# pcbthing.net
KiCad netlist of a schematic drawn in Altium Designer
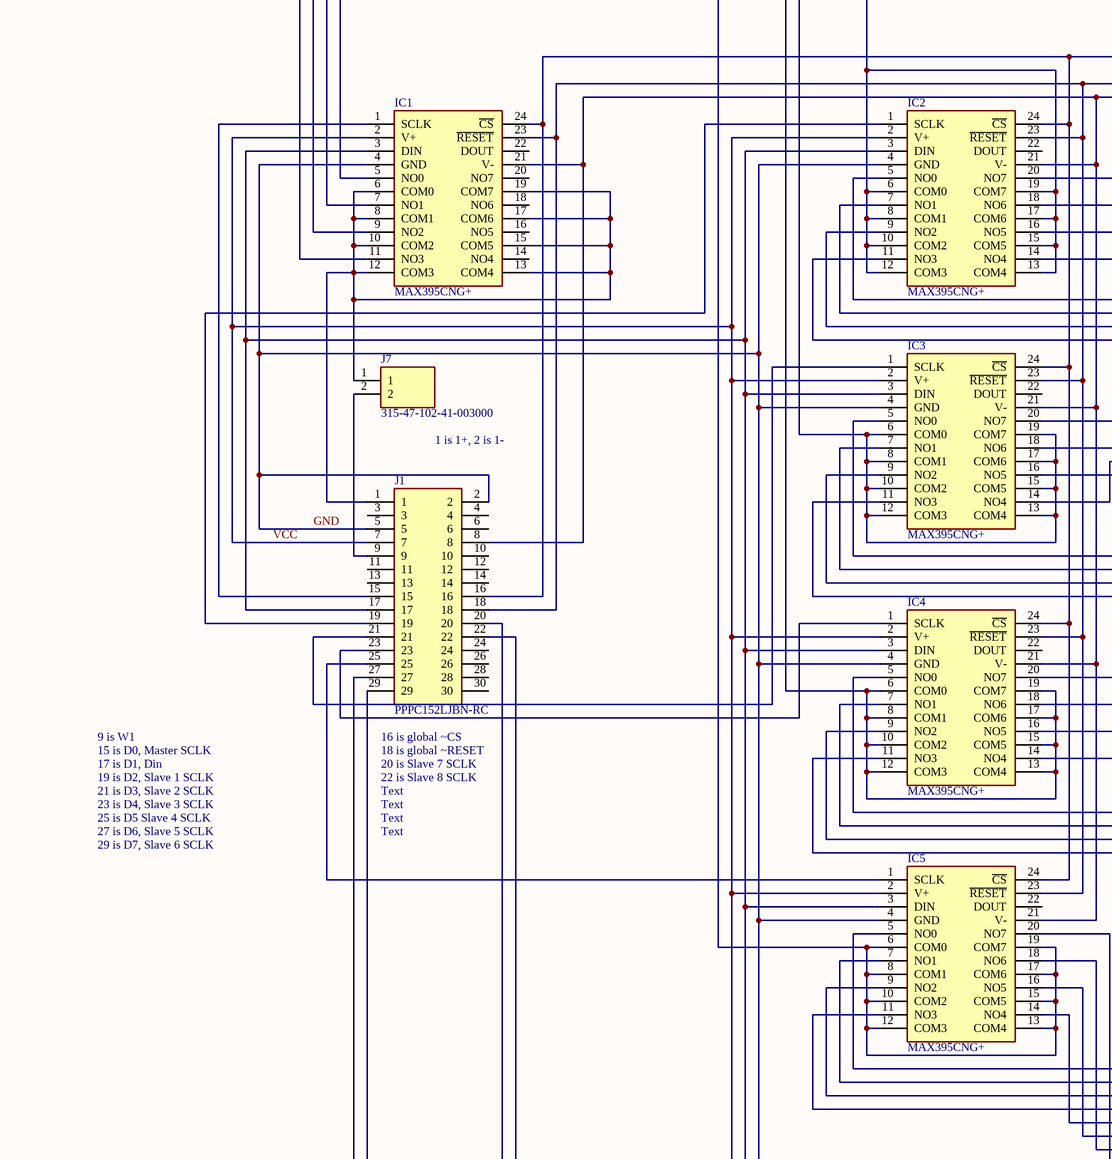
[diagram p0: pcbthing.SchDoc, left]
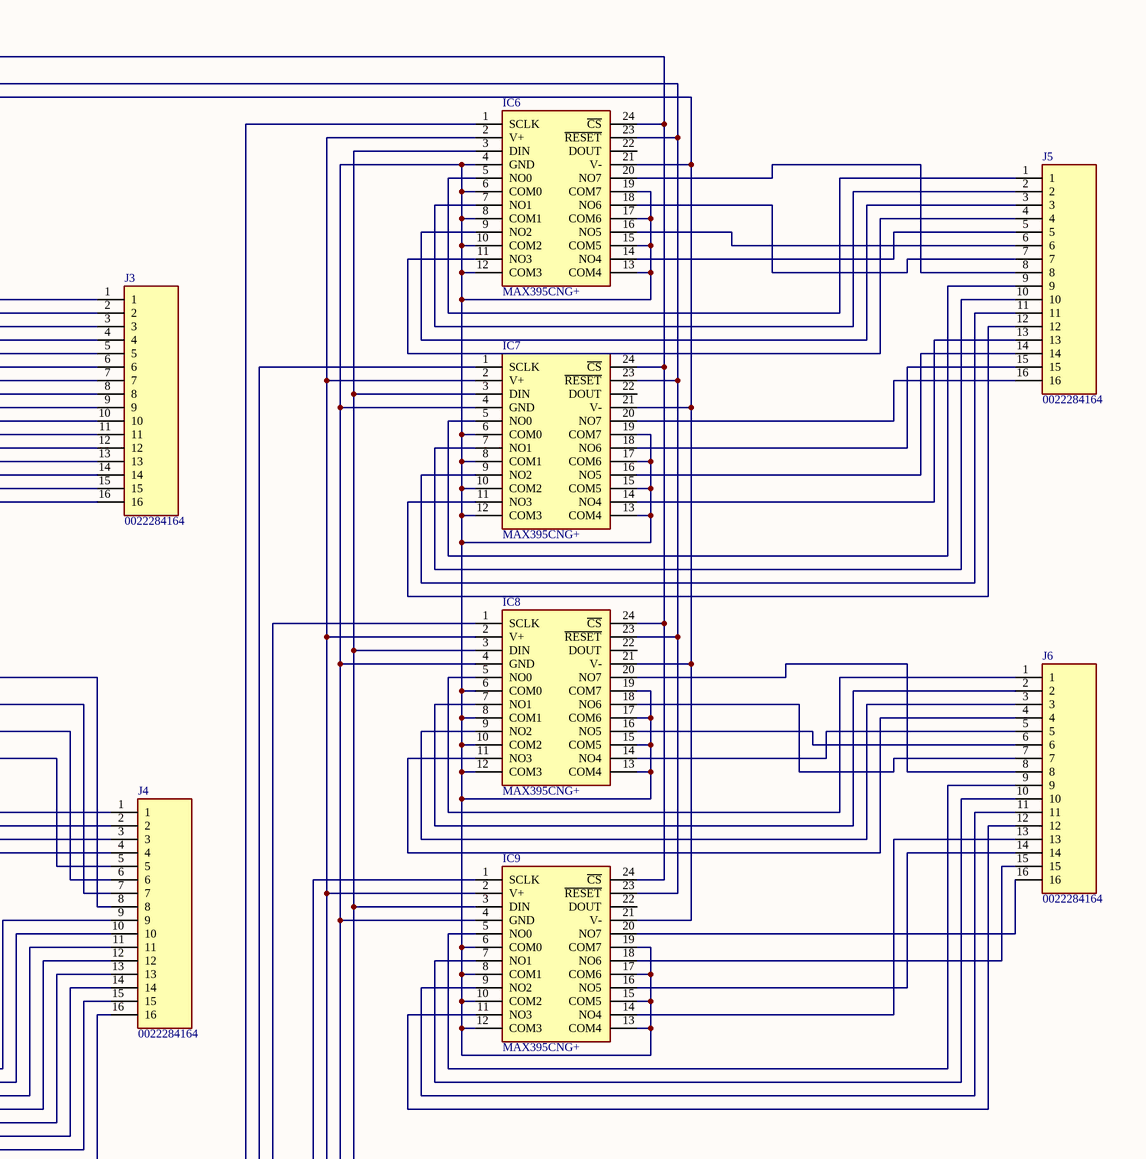
[diagram p1: pcbthing.SchDoc, right]

(export (version "E")
  (design (tool "Eeschema 10.0.6"))
  (components
    (comp (ref "IC1")
      (value "MAX395CNG+")
      (footprint "SamacSys:DIP794W56P254L3054H457Q24N")
      (description "Integrated Circuit")
      (fields (field (name "MOUSER PART NUMBER") "700-MAX395CNG"))
      (libsource (lib "*") (part "MAX395CNG+"))
    )
    (comp (ref "IC2")
      (value "MAX395CNG+")
      (footprint "SamacSys:DIP794W56P254L3054H457Q24N")
      (description "Integrated Circuit")
      (fields (field (name "MOUSER PART NUMBER") "700-MAX395CNG"))
      (libsource (lib "*") (part "MAX395CNG+"))
    )
    (comp (ref "IC3")
      (value "MAX395CNG+")
      (footprint "SamacSys:DIP794W56P254L3054H457Q24N")
      (description "Integrated Circuit")
      (fields (field (name "MOUSER PART NUMBER") "700-MAX395CNG"))
      (libsource (lib "*") (part "MAX395CNG+"))
    )
    (comp (ref "IC4")
      (value "MAX395CNG+")
      (footprint "SamacSys:DIP794W56P254L3054H457Q24N")
      (description "Integrated Circuit")
      (fields (field (name "MOUSER PART NUMBER") "700-MAX395CNG"))
      (libsource (lib "*") (part "MAX395CNG+"))
    )
    (comp (ref "IC5")
      (value "MAX395CNG+")
      (footprint "SamacSys:DIP794W56P254L3054H457Q24N")
      (description "Integrated Circuit")
      (fields (field (name "MOUSER PART NUMBER") "700-MAX395CNG"))
      (libsource (lib "*") (part "MAX395CNG+"))
    )
    (comp (ref "IC6")
      (value "MAX395CNG+")
      (footprint "SamacSys:DIP794W56P254L3054H457Q24N")
      (description "Integrated Circuit")
      (fields (field (name "MOUSER PART NUMBER") "700-MAX395CNG"))
      (libsource (lib "*") (part "MAX395CNG+"))
    )
    (comp (ref "IC7")
      (value "MAX395CNG+")
      (footprint "SamacSys:DIP794W56P254L3054H457Q24N")
      (description "Integrated Circuit")
      (fields (field (name "MOUSER PART NUMBER") "700-MAX395CNG"))
      (libsource (lib "*") (part "MAX395CNG+"))
    )
    (comp (ref "IC8")
      (value "MAX395CNG+")
      (footprint "SamacSys:DIP794W56P254L3054H457Q24N")
      (description "Integrated Circuit")
      (fields (field (name "MOUSER PART NUMBER") "700-MAX395CNG"))
      (libsource (lib "*") (part "MAX395CNG+"))
    )
    (comp (ref "IC9")
      (value "MAX395CNG+")
      (footprint "SamacSys:DIP794W56P254L3054H457Q24N")
      (description "Integrated Circuit")
      (fields (field (name "MOUSER PART NUMBER") "700-MAX395CNG"))
      (libsource (lib "*") (part "MAX395CNG+"))
    )
    (comp (ref "J1")
      (value "PPPC152LJBN-RC")
      (footprint "SamacSys:RHDRRA30W60P254X254_2X15_3860X850X528P")
      (description "Connector")
      (libsource (lib "*") (part "PPPC152LJBN-RC"))
    )
    (comp (ref "J3")
      (value "0022284164")
      (footprint "SamacSys:HDRV16W66P0X254_1X16_4064X249X1041P")
      (description "Connector")
      (libsource (lib "*") (part "0022284164"))
    )
    (comp (ref "J4")
      (value "0022284164")
      (footprint "SamacSys:HDRV16W66P0X254_1X16_4064X249X1041P")
      (description "Connector")
      (libsource (lib "*") (part "0022284164"))
    )
    (comp (ref "J5")
      (value "0022284164")
      (footprint "SamacSys:HDRV16W66P0X254_1X16_4064X249X1041P")
      (description "Connector")
      (libsource (lib "*") (part "0022284164"))
    )
    (comp (ref "J6")
      (value "0022284164")
      (footprint "SamacSys:HDRV16W66P0X254_1X16_4064X249X1041P")
      (description "Connector")
      (libsource (lib "*") (part "0022284164"))
    )
    (comp (ref "J7")
      (value "315-47-102-41-003000")
      (footprint "SamacSys:3154710241003000")
      (description "Connector")
      (fields (field (name "MOUSER PART NUMBER") "575-3154710241003000"))
      (libsource (lib "*") (part "315-47-102-41-003000"))
    )
  )
  (nets
    (net (code "1") (name "/GND") (class "Default")
      (node (ref "IC1") (pin "4") (pinfunction "GND_4") (pintype "passive"))
      (node (ref "IC2") (pin "4") (pinfunction "GND_4") (pintype "passive"))
      (node (ref "IC3") (pin "4") (pinfunction "GND_4") (pintype "passive"))
      (node (ref "IC4") (pin "4") (pinfunction "GND_4") (pintype "passive"))
      (node (ref "IC5") (pin "4") (pinfunction "GND_4") (pintype "passive"))
      (node (ref "IC6") (pin "10") (pinfunction "COM2_10") (pintype "passive"))
      (node (ref "IC6") (pin "12") (pinfunction "COM3_12") (pintype "passive"))
      (node (ref "IC6") (pin "13") (pinfunction "COM4_13") (pintype "passive"))
      (node (ref "IC6") (pin "15") (pinfunction "COM5_15") (pintype "passive"))
      (node (ref "IC6") (pin "17") (pinfunction "COM6_17") (pintype "passive"))
      (node (ref "IC6") (pin "19") (pinfunction "COM7_19") (pintype "passive"))
      (node (ref "IC6") (pin "4") (pinfunction "GND_4") (pintype "passive"))
      (node (ref "IC6") (pin "6") (pinfunction "COM0_6") (pintype "passive"))
      (node (ref "IC6") (pin "8") (pinfunction "COM1_8") (pintype "passive"))
      (node (ref "IC7") (pin "10") (pinfunction "COM2_10") (pintype "passive"))
      (node (ref "IC7") (pin "12") (pinfunction "COM3_12") (pintype "passive"))
      (node (ref "IC7") (pin "13") (pinfunction "COM4_13") (pintype "passive"))
      (node (ref "IC7") (pin "15") (pinfunction "COM5_15") (pintype "passive"))
      (node (ref "IC7") (pin "17") (pinfunction "COM6_17") (pintype "passive"))
      (node (ref "IC7") (pin "19") (pinfunction "COM7_19") (pintype "passive"))
      (node (ref "IC7") (pin "4") (pinfunction "GND_4") (pintype "passive"))
      (node (ref "IC7") (pin "6") (pinfunction "COM0_6") (pintype "passive"))
      (node (ref "IC7") (pin "8") (pinfunction "COM1_8") (pintype "passive"))
      (node (ref "IC8") (pin "10") (pinfunction "COM2_10") (pintype "passive"))
      (node (ref "IC8") (pin "12") (pinfunction "COM3_12") (pintype "passive"))
      (node (ref "IC8") (pin "13") (pinfunction "COM4_13") (pintype "passive"))
      (node (ref "IC8") (pin "15") (pinfunction "COM5_15") (pintype "passive"))
      (node (ref "IC8") (pin "17") (pinfunction "COM6_17") (pintype "passive"))
      (node (ref "IC8") (pin "19") (pinfunction "COM7_19") (pintype "passive"))
      (node (ref "IC8") (pin "4") (pinfunction "GND_4") (pintype "passive"))
      (node (ref "IC8") (pin "6") (pinfunction "COM0_6") (pintype "passive"))
      (node (ref "IC8") (pin "8") (pinfunction "COM1_8") (pintype "passive"))
      (node (ref "IC9") (pin "10") (pinfunction "COM2_10") (pintype "passive"))
      (node (ref "IC9") (pin "12") (pinfunction "COM3_12") (pintype "passive"))
      (node (ref "IC9") (pin "13") (pinfunction "COM4_13") (pintype "passive"))
      (node (ref "IC9") (pin "15") (pinfunction "COM5_15") (pintype "passive"))
      (node (ref "IC9") (pin "17") (pinfunction "COM6_17") (pintype "passive"))
      (node (ref "IC9") (pin "19") (pinfunction "COM7_19") (pintype "passive"))
      (node (ref "IC9") (pin "4") (pinfunction "GND_4") (pintype "passive"))
      (node (ref "IC9") (pin "6") (pinfunction "COM0_6") (pintype "passive"))
      (node (ref "IC9") (pin "8") (pinfunction "COM1_8") (pintype "passive"))
      (node (ref "J1") (pin "2") (pinfunction "2_2") (pintype "passive"))
      (node (ref "J1") (pin "5") (pinfunction "5_5") (pintype "passive"))
    )
    (net (code "2") (name "/VCC") (class "Default")
      (node (ref "IC1") (pin "2") (pinfunction "V+_2") (pintype "passive"))
      (node (ref "IC2") (pin "2") (pinfunction "V+_2") (pintype "passive"))
      (node (ref "IC3") (pin "2") (pinfunction "V+_2") (pintype "passive"))
      (node (ref "IC4") (pin "2") (pinfunction "V+_2") (pintype "passive"))
      (node (ref "IC5") (pin "2") (pinfunction "V+_2") (pintype "passive"))
      (node (ref "IC6") (pin "2") (pinfunction "V+_2") (pintype "passive"))
      (node (ref "IC7") (pin "2") (pinfunction "V+_2") (pintype "passive"))
      (node (ref "IC8") (pin "2") (pinfunction "V+_2") (pintype "passive"))
      (node (ref "IC9") (pin "2") (pinfunction "V+_2") (pintype "passive"))
      (node (ref "J1") (pin "7") (pinfunction "7_7") (pintype "passive"))
    )
    (net (code "3") (name "Net-(IC1-COM0)") (class "Default")
      (node (ref "IC1") (pin "10") (pinfunction "COM2_10") (pintype "passive"))
      (node (ref "IC1") (pin "12") (pinfunction "COM3_12") (pintype "passive"))
      (node (ref "IC1") (pin "13") (pinfunction "COM4_13") (pintype "passive"))
      (node (ref "IC1") (pin "15") (pinfunction "COM5_15") (pintype "passive"))
      (node (ref "IC1") (pin "17") (pinfunction "COM6_17") (pintype "passive"))
      (node (ref "IC1") (pin "19") (pinfunction "COM7_19") (pintype "passive"))
      (node (ref "IC1") (pin "6") (pinfunction "COM0_6") (pintype "passive"))
      (node (ref "IC1") (pin "8") (pinfunction "COM1_8") (pintype "passive"))
      (node (ref "J1") (pin "1") (pinfunction "1_1") (pintype "passive"))
      (node (ref "J7") (pin "1") (pinfunction "1_1") (pintype "passive"))
    )
    (net (code "4") (name "Net-(IC1-DIN)") (class "Default")
      (node (ref "IC1") (pin "3") (pinfunction "DIN_3") (pintype "passive"))
      (node (ref "IC2") (pin "3") (pinfunction "DIN_3") (pintype "passive"))
      (node (ref "IC3") (pin "3") (pinfunction "DIN_3") (pintype "passive"))
      (node (ref "IC4") (pin "3") (pinfunction "DIN_3") (pintype "passive"))
      (node (ref "IC5") (pin "3") (pinfunction "DIN_3") (pintype "passive"))
      (node (ref "IC6") (pin "3") (pinfunction "DIN_3") (pintype "passive"))
      (node (ref "IC7") (pin "3") (pinfunction "DIN_3") (pintype "passive"))
      (node (ref "IC8") (pin "3") (pinfunction "DIN_3") (pintype "passive"))
      (node (ref "IC9") (pin "3") (pinfunction "DIN_3") (pintype "passive"))
      (node (ref "J1") (pin "17") (pinfunction "17_17") (pintype "passive"))
    )
    (net (code "5") (name "Net-(IC1-NO0)") (class "Default")
      (node (ref "IC1") (pin "5") (pinfunction "NO0_5") (pintype "passive"))
      (node (ref "IC2") (pin "10") (pinfunction "COM2_10") (pintype "passive"))
      (node (ref "IC2") (pin "12") (pinfunction "COM3_12") (pintype "passive"))
      (node (ref "IC2") (pin "13") (pinfunction "COM4_13") (pintype "passive"))
      (node (ref "IC2") (pin "15") (pinfunction "COM5_15") (pintype "passive"))
      (node (ref "IC2") (pin "17") (pinfunction "COM6_17") (pintype "passive"))
      (node (ref "IC2") (pin "19") (pinfunction "COM7_19") (pintype "passive"))
      (node (ref "IC2") (pin "6") (pinfunction "COM0_6") (pintype "passive"))
      (node (ref "IC2") (pin "8") (pinfunction "COM1_8") (pintype "passive"))
    )
    (net (code "6") (name "Net-(IC1-NO1)") (class "Default")
      (node (ref "IC1") (pin "7") (pinfunction "NO1_7") (pintype "passive"))
      (node (ref "IC3") (pin "10") (pinfunction "COM2_10") (pintype "passive"))
      (node (ref "IC3") (pin "12") (pinfunction "COM3_12") (pintype "passive"))
      (node (ref "IC3") (pin "13") (pinfunction "COM4_13") (pintype "passive"))
      (node (ref "IC3") (pin "15") (pinfunction "COM5_15") (pintype "passive"))
      (node (ref "IC3") (pin "17") (pinfunction "COM6_17") (pintype "passive"))
      (node (ref "IC3") (pin "19") (pinfunction "COM7_19") (pintype "passive"))
      (node (ref "IC3") (pin "6") (pinfunction "COM0_6") (pintype "passive"))
      (node (ref "IC3") (pin "8") (pinfunction "COM1_8") (pintype "passive"))
    )
    (net (code "7") (name "Net-(IC1-NO2)") (class "Default")
      (node (ref "IC1") (pin "9") (pinfunction "NO2_9") (pintype "passive"))
      (node (ref "IC4") (pin "10") (pinfunction "COM2_10") (pintype "passive"))
      (node (ref "IC4") (pin "12") (pinfunction "COM3_12") (pintype "passive"))
      (node (ref "IC4") (pin "13") (pinfunction "COM4_13") (pintype "passive"))
      (node (ref "IC4") (pin "15") (pinfunction "COM5_15") (pintype "passive"))
      (node (ref "IC4") (pin "17") (pinfunction "COM6_17") (pintype "passive"))
      (node (ref "IC4") (pin "19") (pinfunction "COM7_19") (pintype "passive"))
      (node (ref "IC4") (pin "6") (pinfunction "COM0_6") (pintype "passive"))
      (node (ref "IC4") (pin "8") (pinfunction "COM1_8") (pintype "passive"))
    )
    (net (code "8") (name "Net-(IC1-NO3)") (class "Default")
      (node (ref "IC1") (pin "11") (pinfunction "NO3_11") (pintype "passive"))
      (node (ref "IC5") (pin "10") (pinfunction "COM2_10") (pintype "passive"))
      (node (ref "IC5") (pin "12") (pinfunction "COM3_12") (pintype "passive"))
      (node (ref "IC5") (pin "13") (pinfunction "COM4_13") (pintype "passive"))
      (node (ref "IC5") (pin "15") (pinfunction "COM5_15") (pintype "passive"))
      (node (ref "IC5") (pin "17") (pinfunction "COM6_17") (pintype "passive"))
      (node (ref "IC5") (pin "19") (pinfunction "COM7_19") (pintype "passive"))
      (node (ref "IC5") (pin "6") (pinfunction "COM0_6") (pintype "passive"))
      (node (ref "IC5") (pin "8") (pinfunction "COM1_8") (pintype "passive"))
    )
    (net (code "9") (name "Net-(IC1-SCLK)") (class "Default")
      (node (ref "IC1") (pin "1") (pinfunction "SCLK_1") (pintype "passive"))
      (node (ref "J1") (pin "15") (pinfunction "15_15") (pintype "passive"))
    )
    (net (code "10") (name "Net-(IC1-V-)") (class "Default")
      (node (ref "IC1") (pin "21") (pinfunction "V-_21") (pintype "passive"))
      (node (ref "IC2") (pin "21") (pinfunction "V-_21") (pintype "passive"))
      (node (ref "IC3") (pin "21") (pinfunction "V-_21") (pintype "passive"))
      (node (ref "IC4") (pin "21") (pinfunction "V-_21") (pintype "passive"))
      (node (ref "IC5") (pin "21") (pinfunction "V-_21") (pintype "passive"))
      (node (ref "IC6") (pin "21") (pinfunction "V-_21") (pintype "passive"))
      (node (ref "IC7") (pin "21") (pinfunction "V-_21") (pintype "passive"))
      (node (ref "IC8") (pin "21") (pinfunction "V-_21") (pintype "passive"))
      (node (ref "IC9") (pin "21") (pinfunction "V-_21") (pintype "passive"))
      (node (ref "J1") (pin "8") (pinfunction "8_8") (pintype "passive"))
    )
    (net (code "11") (name "Net-(IC1-~{CS})") (class "Default")
      (node (ref "IC1") (pin "24") (pinfunction "~{CS}_24") (pintype "passive"))
      (node (ref "IC2") (pin "24") (pinfunction "~{CS}_24") (pintype "passive"))
      (node (ref "IC3") (pin "24") (pinfunction "~{CS}_24") (pintype "passive"))
      (node (ref "IC4") (pin "24") (pinfunction "~{CS}_24") (pintype "passive"))
      (node (ref "IC5") (pin "24") (pinfunction "~{CS}_24") (pintype "passive"))
      (node (ref "IC6") (pin "24") (pinfunction "~{CS}_24") (pintype "passive"))
      (node (ref "IC7") (pin "24") (pinfunction "~{CS}_24") (pintype "passive"))
      (node (ref "IC8") (pin "24") (pinfunction "~{CS}_24") (pintype "passive"))
      (node (ref "IC9") (pin "24") (pinfunction "~{CS}_24") (pintype "passive"))
      (node (ref "J1") (pin "16") (pinfunction "16_16") (pintype "passive"))
    )
    (net (code "12") (name "Net-(IC1-~{RESET})") (class "Default")
      (node (ref "IC1") (pin "23") (pinfunction "~{RESET}_23") (pintype "passive"))
      (node (ref "IC2") (pin "23") (pinfunction "~{RESET}_23") (pintype "passive"))
      (node (ref "IC3") (pin "23") (pinfunction "~{RESET}_23") (pintype "passive"))
      (node (ref "IC4") (pin "23") (pinfunction "~{RESET}_23") (pintype "passive"))
      (node (ref "IC5") (pin "23") (pinfunction "~{RESET}_23") (pintype "passive"))
      (node (ref "IC6") (pin "23") (pinfunction "~{RESET}_23") (pintype "passive"))
      (node (ref "IC7") (pin "23") (pinfunction "~{RESET}_23") (pintype "passive"))
      (node (ref "IC8") (pin "23") (pinfunction "~{RESET}_23") (pintype "passive"))
      (node (ref "IC9") (pin "23") (pinfunction "~{RESET}_23") (pintype "passive"))
      (node (ref "J1") (pin "18") (pinfunction "18_18") (pintype "passive"))
    )
    (net (code "13") (name "Net-(IC2-NO0)") (class "Default")
      (node (ref "IC2") (pin "5") (pinfunction "NO0_5") (pintype "passive"))
      (node (ref "J3") (pin "1") (pinfunction "1_1") (pintype "passive"))
    )
    (net (code "14") (name "Net-(IC2-NO1)") (class "Default")
      (node (ref "IC2") (pin "7") (pinfunction "NO1_7") (pintype "passive"))
      (node (ref "J3") (pin "2") (pinfunction "2_2") (pintype "passive"))
    )
    (net (code "15") (name "Net-(IC2-NO2)") (class "Default")
      (node (ref "IC2") (pin "9") (pinfunction "NO2_9") (pintype "passive"))
      (node (ref "J3") (pin "3") (pinfunction "3_3") (pintype "passive"))
    )
    (net (code "16") (name "Net-(IC2-NO3)") (class "Default")
      (node (ref "IC2") (pin "11") (pinfunction "NO3_11") (pintype "passive"))
      (node (ref "J3") (pin "4") (pinfunction "4_4") (pintype "passive"))
    )
    (net (code "17") (name "Net-(IC2-NO4)") (class "Default")
      (node (ref "IC2") (pin "14") (pinfunction "NO4_14") (pintype "passive"))
      (node (ref "J3") (pin "5") (pinfunction "5_5") (pintype "passive"))
    )
    (net (code "18") (name "Net-(IC2-NO5)") (class "Default")
      (node (ref "IC2") (pin "16") (pinfunction "NO5_16") (pintype "passive"))
      (node (ref "J3") (pin "6") (pinfunction "6_6") (pintype "passive"))
    )
    (net (code "19") (name "Net-(IC2-NO6)") (class "Default")
      (node (ref "IC2") (pin "18") (pinfunction "NO6_18") (pintype "passive"))
      (node (ref "J3") (pin "7") (pinfunction "7_7") (pintype "passive"))
    )
    (net (code "20") (name "Net-(IC2-NO7)") (class "Default")
      (node (ref "IC2") (pin "20") (pinfunction "NO7_20") (pintype "passive"))
      (node (ref "J3") (pin "8") (pinfunction "8_8") (pintype "passive"))
    )
    (net (code "21") (name "Net-(IC2-SCLK)") (class "Default")
      (node (ref "IC2") (pin "1") (pinfunction "SCLK_1") (pintype "passive"))
      (node (ref "J1") (pin "19") (pinfunction "19_19") (pintype "passive"))
    )
    (net (code "22") (name "Net-(IC3-NO0)") (class "Default")
      (node (ref "IC3") (pin "5") (pinfunction "NO0_5") (pintype "passive"))
      (node (ref "J3") (pin "9") (pinfunction "9_9") (pintype "passive"))
    )
    (net (code "23") (name "Net-(IC3-NO1)") (class "Default")
      (node (ref "IC3") (pin "7") (pinfunction "NO1_7") (pintype "passive"))
      (node (ref "J3") (pin "10") (pinfunction "10_10") (pintype "passive"))
    )
    (net (code "24") (name "Net-(IC3-NO2)") (class "Default")
      (node (ref "IC3") (pin "9") (pinfunction "NO2_9") (pintype "passive"))
      (node (ref "J3") (pin "11") (pinfunction "11_11") (pintype "passive"))
    )
    (net (code "25") (name "Net-(IC3-NO3)") (class "Default")
      (node (ref "IC3") (pin "11") (pinfunction "NO3_11") (pintype "passive"))
      (node (ref "J3") (pin "12") (pinfunction "12_12") (pintype "passive"))
    )
    (net (code "26") (name "Net-(IC3-NO4)") (class "Default")
      (node (ref "IC3") (pin "14") (pinfunction "NO4_14") (pintype "passive"))
      (node (ref "J3") (pin "13") (pinfunction "13_13") (pintype "passive"))
    )
    (net (code "27") (name "Net-(IC3-NO5)") (class "Default")
      (node (ref "IC3") (pin "16") (pinfunction "NO5_16") (pintype "passive"))
      (node (ref "J3") (pin "14") (pinfunction "14_14") (pintype "passive"))
    )
    (net (code "28") (name "Net-(IC3-NO6)") (class "Default")
      (node (ref "IC3") (pin "18") (pinfunction "NO6_18") (pintype "passive"))
      (node (ref "J3") (pin "15") (pinfunction "15_15") (pintype "passive"))
    )
    (net (code "29") (name "Net-(IC3-NO7)") (class "Default")
      (node (ref "IC3") (pin "20") (pinfunction "NO7_20") (pintype "passive"))
      (node (ref "J3") (pin "16") (pinfunction "16_16") (pintype "passive"))
    )
    (net (code "30") (name "Net-(IC3-SCLK)") (class "Default")
      (node (ref "IC3") (pin "1") (pinfunction "SCLK_1") (pintype "passive"))
      (node (ref "J1") (pin "21") (pinfunction "21_21") (pintype "passive"))
    )
    (net (code "31") (name "Net-(IC4-NO0)") (class "Default")
      (node (ref "IC4") (pin "5") (pinfunction "NO0_5") (pintype "passive"))
      (node (ref "J4") (pin "1") (pinfunction "1_1") (pintype "passive"))
    )
    (net (code "32") (name "Net-(IC4-NO1)") (class "Default")
      (node (ref "IC4") (pin "7") (pinfunction "NO1_7") (pintype "passive"))
      (node (ref "J4") (pin "2") (pinfunction "2_2") (pintype "passive"))
    )
    (net (code "33") (name "Net-(IC4-NO2)") (class "Default")
      (node (ref "IC4") (pin "9") (pinfunction "NO2_9") (pintype "passive"))
      (node (ref "J4") (pin "3") (pinfunction "3_3") (pintype "passive"))
    )
    (net (code "34") (name "Net-(IC4-NO3)") (class "Default")
      (node (ref "IC4") (pin "11") (pinfunction "NO3_11") (pintype "passive"))
      (node (ref "J4") (pin "4") (pinfunction "4_4") (pintype "passive"))
    )
    (net (code "35") (name "Net-(IC4-NO4)") (class "Default")
      (node (ref "IC4") (pin "14") (pinfunction "NO4_14") (pintype "passive"))
      (node (ref "J4") (pin "5") (pinfunction "5_5") (pintype "passive"))
    )
    (net (code "36") (name "Net-(IC4-NO5)") (class "Default")
      (node (ref "IC4") (pin "16") (pinfunction "NO5_16") (pintype "passive"))
      (node (ref "J4") (pin "6") (pinfunction "6_6") (pintype "passive"))
    )
    (net (code "37") (name "Net-(IC4-NO6)") (class "Default")
      (node (ref "IC4") (pin "18") (pinfunction "NO6_18") (pintype "passive"))
      (node (ref "J4") (pin "7") (pinfunction "7_7") (pintype "passive"))
    )
    (net (code "38") (name "Net-(IC4-NO7)") (class "Default")
      (node (ref "IC4") (pin "20") (pinfunction "NO7_20") (pintype "passive"))
      (node (ref "J4") (pin "8") (pinfunction "8_8") (pintype "passive"))
    )
    (net (code "39") (name "Net-(IC4-SCLK)") (class "Default")
      (node (ref "IC4") (pin "1") (pinfunction "SCLK_1") (pintype "passive"))
      (node (ref "J1") (pin "23") (pinfunction "23_23") (pintype "passive"))
    )
    (net (code "40") (name "Net-(IC5-NO0)") (class "Default")
      (node (ref "IC5") (pin "5") (pinfunction "NO0_5") (pintype "passive"))
      (node (ref "J4") (pin "9") (pinfunction "9_9") (pintype "passive"))
    )
    (net (code "41") (name "Net-(IC5-NO1)") (class "Default")
      (node (ref "IC5") (pin "7") (pinfunction "NO1_7") (pintype "passive"))
      (node (ref "J4") (pin "10") (pinfunction "10_10") (pintype "passive"))
    )
    (net (code "42") (name "Net-(IC5-NO2)") (class "Default")
      (node (ref "IC5") (pin "9") (pinfunction "NO2_9") (pintype "passive"))
      (node (ref "J4") (pin "11") (pinfunction "11_11") (pintype "passive"))
    )
    (net (code "43") (name "Net-(IC5-NO3)") (class "Default")
      (node (ref "IC5") (pin "11") (pinfunction "NO3_11") (pintype "passive"))
      (node (ref "J4") (pin "12") (pinfunction "12_12") (pintype "passive"))
    )
    (net (code "44") (name "Net-(IC5-NO4)") (class "Default")
      (node (ref "IC5") (pin "14") (pinfunction "NO4_14") (pintype "passive"))
      (node (ref "J4") (pin "13") (pinfunction "13_13") (pintype "passive"))
    )
    (net (code "45") (name "Net-(IC5-NO5)") (class "Default")
      (node (ref "IC5") (pin "16") (pinfunction "NO5_16") (pintype "passive"))
      (node (ref "J4") (pin "14") (pinfunction "14_14") (pintype "passive"))
    )
    (net (code "46") (name "Net-(IC5-NO6)") (class "Default")
      (node (ref "IC5") (pin "18") (pinfunction "NO6_18") (pintype "passive"))
      (node (ref "J4") (pin "15") (pinfunction "15_15") (pintype "passive"))
    )
    (net (code "47") (name "Net-(IC5-NO7)") (class "Default")
      (node (ref "IC5") (pin "20") (pinfunction "NO7_20") (pintype "passive"))
      (node (ref "J4") (pin "16") (pinfunction "16_16") (pintype "passive"))
    )
    (net (code "48") (name "Net-(IC5-SCLK)") (class "Default")
      (node (ref "IC5") (pin "1") (pinfunction "SCLK_1") (pintype "passive"))
      (node (ref "J1") (pin "25") (pinfunction "25_25") (pintype "passive"))
    )
    (net (code "49") (name "Net-(IC6-NO0)") (class "Default")
      (node (ref "IC6") (pin "5") (pinfunction "NO0_5") (pintype "passive"))
      (node (ref "J5") (pin "1") (pinfunction "1_1") (pintype "passive"))
    )
    (net (code "50") (name "Net-(IC6-NO1)") (class "Default")
      (node (ref "IC6") (pin "7") (pinfunction "NO1_7") (pintype "passive"))
      (node (ref "J5") (pin "2") (pinfunction "2_2") (pintype "passive"))
    )
    (net (code "51") (name "Net-(IC6-NO2)") (class "Default")
      (node (ref "IC6") (pin "9") (pinfunction "NO2_9") (pintype "passive"))
      (node (ref "J5") (pin "3") (pinfunction "3_3") (pintype "passive"))
    )
    (net (code "52") (name "Net-(IC6-NO3)") (class "Default")
      (node (ref "IC6") (pin "11") (pinfunction "NO3_11") (pintype "passive"))
      (node (ref "J5") (pin "4") (pinfunction "4_4") (pintype "passive"))
    )
    (net (code "53") (name "Net-(IC6-NO4)") (class "Default")
      (node (ref "IC6") (pin "14") (pinfunction "NO4_14") (pintype "passive"))
      (node (ref "J5") (pin "5") (pinfunction "5_5") (pintype "passive"))
    )
    (net (code "54") (name "Net-(IC6-NO5)") (class "Default")
      (node (ref "IC6") (pin "16") (pinfunction "NO5_16") (pintype "passive"))
      (node (ref "J5") (pin "6") (pinfunction "6_6") (pintype "passive"))
    )
    (net (code "55") (name "Net-(IC6-NO6)") (class "Default")
      (node (ref "IC6") (pin "18") (pinfunction "NO6_18") (pintype "passive"))
      (node (ref "J5") (pin "7") (pinfunction "7_7") (pintype "passive"))
    )
    (net (code "56") (name "Net-(IC6-NO7)") (class "Default")
      (node (ref "IC6") (pin "20") (pinfunction "NO7_20") (pintype "passive"))
      (node (ref "J5") (pin "8") (pinfunction "8_8") (pintype "passive"))
    )
    (net (code "57") (name "Net-(IC6-SCLK)") (class "Default")
      (node (ref "IC6") (pin "1") (pinfunction "SCLK_1") (pintype "passive"))
      (node (ref "J1") (pin "27") (pinfunction "27_27") (pintype "passive"))
    )
    (net (code "58") (name "Net-(IC7-NO0)") (class "Default")
      (node (ref "IC7") (pin "5") (pinfunction "NO0_5") (pintype "passive"))
      (node (ref "J5") (pin "9") (pinfunction "9_9") (pintype "passive"))
    )
    (net (code "59") (name "Net-(IC7-NO1)") (class "Default")
      (node (ref "IC7") (pin "7") (pinfunction "NO1_7") (pintype "passive"))
      (node (ref "J5") (pin "10") (pinfunction "10_10") (pintype "passive"))
    )
    (net (code "60") (name "Net-(IC7-NO2)") (class "Default")
      (node (ref "IC7") (pin "9") (pinfunction "NO2_9") (pintype "passive"))
      (node (ref "J5") (pin "11") (pinfunction "11_11") (pintype "passive"))
    )
    (net (code "61") (name "Net-(IC7-NO3)") (class "Default")
      (node (ref "IC7") (pin "11") (pinfunction "NO3_11") (pintype "passive"))
      (node (ref "J5") (pin "12") (pinfunction "12_12") (pintype "passive"))
    )
    (net (code "62") (name "Net-(IC7-NO4)") (class "Default")
      (node (ref "IC7") (pin "14") (pinfunction "NO4_14") (pintype "passive"))
      (node (ref "J5") (pin "13") (pinfunction "13_13") (pintype "passive"))
    )
    (net (code "63") (name "Net-(IC7-NO5)") (class "Default")
      (node (ref "IC7") (pin "16") (pinfunction "NO5_16") (pintype "passive"))
      (node (ref "J5") (pin "14") (pinfunction "14_14") (pintype "passive"))
    )
    (net (code "64") (name "Net-(IC7-NO6)") (class "Default")
      (node (ref "IC7") (pin "18") (pinfunction "NO6_18") (pintype "passive"))
      (node (ref "J5") (pin "15") (pinfunction "15_15") (pintype "passive"))
    )
    (net (code "65") (name "Net-(IC7-NO7)") (class "Default")
      (node (ref "IC7") (pin "20") (pinfunction "NO7_20") (pintype "passive"))
      (node (ref "J5") (pin "16") (pinfunction "16_16") (pintype "passive"))
    )
    (net (code "66") (name "Net-(IC7-SCLK)") (class "Default")
      (node (ref "IC7") (pin "1") (pinfunction "SCLK_1") (pintype "passive"))
      (node (ref "J1") (pin "29") (pinfunction "29_29") (pintype "passive"))
    )
    (net (code "67") (name "Net-(IC8-NO0)") (class "Default")
      (node (ref "IC8") (pin "5") (pinfunction "NO0_5") (pintype "passive"))
      (node (ref "J6") (pin "1") (pinfunction "1_1") (pintype "passive"))
    )
    (net (code "68") (name "Net-(IC8-NO1)") (class "Default")
      (node (ref "IC8") (pin "7") (pinfunction "NO1_7") (pintype "passive"))
      (node (ref "J6") (pin "2") (pinfunction "2_2") (pintype "passive"))
    )
    (net (code "69") (name "Net-(IC8-NO2)") (class "Default")
      (node (ref "IC8") (pin "9") (pinfunction "NO2_9") (pintype "passive"))
      (node (ref "J6") (pin "3") (pinfunction "3_3") (pintype "passive"))
    )
    (net (code "70") (name "Net-(IC8-NO3)") (class "Default")
      (node (ref "IC8") (pin "11") (pinfunction "NO3_11") (pintype "passive"))
      (node (ref "J6") (pin "4") (pinfunction "4_4") (pintype "passive"))
    )
    (net (code "71") (name "Net-(IC8-NO4)") (class "Default")
      (node (ref "IC8") (pin "14") (pinfunction "NO4_14") (pintype "passive"))
      (node (ref "J6") (pin "5") (pinfunction "5_5") (pintype "passive"))
    )
    (net (code "72") (name "Net-(IC8-NO5)") (class "Default")
      (node (ref "IC8") (pin "16") (pinfunction "NO5_16") (pintype "passive"))
      (node (ref "J6") (pin "6") (pinfunction "6_6") (pintype "passive"))
    )
    (net (code "73") (name "Net-(IC8-NO6)") (class "Default")
      (node (ref "IC8") (pin "18") (pinfunction "NO6_18") (pintype "passive"))
      (node (ref "J6") (pin "7") (pinfunction "7_7") (pintype "passive"))
    )
    (net (code "74") (name "Net-(IC8-NO7)") (class "Default")
      (node (ref "IC8") (pin "20") (pinfunction "NO7_20") (pintype "passive"))
      (node (ref "J6") (pin "8") (pinfunction "8_8") (pintype "passive"))
    )
    (net (code "75") (name "Net-(IC8-SCLK)") (class "Default")
      (node (ref "IC8") (pin "1") (pinfunction "SCLK_1") (pintype "passive"))
      (node (ref "J1") (pin "20") (pinfunction "20_20") (pintype "passive"))
    )
    (net (code "76") (name "Net-(IC9-NO0)") (class "Default")
      (node (ref "IC9") (pin "5") (pinfunction "NO0_5") (pintype "passive"))
      (node (ref "J6") (pin "9") (pinfunction "9_9") (pintype "passive"))
    )
    (net (code "77") (name "Net-(IC9-NO1)") (class "Default")
      (node (ref "IC9") (pin "7") (pinfunction "NO1_7") (pintype "passive"))
      (node (ref "J6") (pin "10") (pinfunction "10_10") (pintype "passive"))
    )
    (net (code "78") (name "Net-(IC9-NO2)") (class "Default")
      (node (ref "IC9") (pin "9") (pinfunction "NO2_9") (pintype "passive"))
      (node (ref "J6") (pin "11") (pinfunction "11_11") (pintype "passive"))
    )
    (net (code "79") (name "Net-(IC9-NO3)") (class "Default")
      (node (ref "IC9") (pin "11") (pinfunction "NO3_11") (pintype "passive"))
      (node (ref "J6") (pin "12") (pinfunction "12_12") (pintype "passive"))
    )
    (net (code "80") (name "Net-(IC9-NO4)") (class "Default")
      (node (ref "IC9") (pin "14") (pinfunction "NO4_14") (pintype "passive"))
      (node (ref "J6") (pin "13") (pinfunction "13_13") (pintype "passive"))
    )
    (net (code "81") (name "Net-(IC9-NO5)") (class "Default")
      (node (ref "IC9") (pin "16") (pinfunction "NO5_16") (pintype "passive"))
      (node (ref "J6") (pin "14") (pinfunction "14_14") (pintype "passive"))
    )
    (net (code "82") (name "Net-(IC9-NO6)") (class "Default")
      (node (ref "IC9") (pin "18") (pinfunction "NO6_18") (pintype "passive"))
      (node (ref "J6") (pin "15") (pinfunction "15_15") (pintype "passive"))
    )
    (net (code "83") (name "Net-(IC9-NO7)") (class "Default")
      (node (ref "IC9") (pin "20") (pinfunction "NO7_20") (pintype "passive"))
      (node (ref "J6") (pin "16") (pinfunction "16_16") (pintype "passive"))
    )
    (net (code "84") (name "Net-(IC9-SCLK)") (class "Default")
      (node (ref "IC9") (pin "1") (pinfunction "SCLK_1") (pintype "passive"))
      (node (ref "J1") (pin "22") (pinfunction "22_22") (pintype "passive"))
    )
    (net (code "85") (name "Net-(J1-Pad9)") (class "Default")
      (node (ref "J1") (pin "9") (pinfunction "9_9") (pintype "passive"))
      (node (ref "J7") (pin "2") (pinfunction "2_2") (pintype "passive"))
    )
    (net (code "86") (name "unconnected-(IC1-DOUT-Pad22)") (class "Default")
      (node (ref "IC1") (pin "22") (pinfunction "DOUT_22") (pintype "passive"))
    )
    (net (code "87") (name "unconnected-(IC1-NO4-Pad14)") (class "Default")
      (node (ref "IC1") (pin "14") (pinfunction "NO4_14") (pintype "passive"))
    )
    (net (code "88") (name "unconnected-(IC1-NO5-Pad16)") (class "Default")
      (node (ref "IC1") (pin "16") (pinfunction "NO5_16") (pintype "passive"))
    )
    (net (code "89") (name "unconnected-(IC1-NO6-Pad18)") (class "Default")
      (node (ref "IC1") (pin "18") (pinfunction "NO6_18") (pintype "passive"))
    )
    (net (code "90") (name "unconnected-(IC1-NO7-Pad20)") (class "Default")
      (node (ref "IC1") (pin "20") (pinfunction "NO7_20") (pintype "passive"))
    )
    (net (code "91") (name "unconnected-(IC2-DOUT-Pad22)") (class "Default")
      (node (ref "IC2") (pin "22") (pinfunction "DOUT_22") (pintype "passive"))
    )
    (net (code "92") (name "unconnected-(IC3-DOUT-Pad22)") (class "Default")
      (node (ref "IC3") (pin "22") (pinfunction "DOUT_22") (pintype "passive"))
    )
    (net (code "93") (name "unconnected-(IC4-DOUT-Pad22)") (class "Default")
      (node (ref "IC4") (pin "22") (pinfunction "DOUT_22") (pintype "passive"))
    )
    (net (code "94") (name "unconnected-(IC5-DOUT-Pad22)") (class "Default")
      (node (ref "IC5") (pin "22") (pinfunction "DOUT_22") (pintype "passive"))
    )
    (net (code "95") (name "unconnected-(IC6-DOUT-Pad22)") (class "Default")
      (node (ref "IC6") (pin "22") (pinfunction "DOUT_22") (pintype "passive"))
    )
    (net (code "96") (name "unconnected-(IC7-DOUT-Pad22)") (class "Default")
      (node (ref "IC7") (pin "22") (pinfunction "DOUT_22") (pintype "passive"))
    )
    (net (code "97") (name "unconnected-(IC8-DOUT-Pad22)") (class "Default")
      (node (ref "IC8") (pin "22") (pinfunction "DOUT_22") (pintype "passive"))
    )
    (net (code "98") (name "unconnected-(IC9-DOUT-Pad22)") (class "Default")
      (node (ref "IC9") (pin "22") (pinfunction "DOUT_22") (pintype "passive"))
    )
    (net (code "99") (name "unconnected-(J1-Pad3)") (class "Default")
      (node (ref "J1") (pin "3") (pinfunction "3_3") (pintype "passive"))
    )
    (net (code "100") (name "unconnected-(J1-Pad4)") (class "Default")
      (node (ref "J1") (pin "4") (pinfunction "4_4") (pintype "passive"))
    )
    (net (code "101") (name "unconnected-(J1-Pad6)") (class "Default")
      (node (ref "J1") (pin "6") (pinfunction "6_6") (pintype "passive"))
    )
    (net (code "102") (name "unconnected-(J1-Pad10)") (class "Default")
      (node (ref "J1") (pin "10") (pinfunction "10_10") (pintype "passive"))
    )
    (net (code "103") (name "unconnected-(J1-Pad11)") (class "Default")
      (node (ref "J1") (pin "11") (pinfunction "11_11") (pintype "passive"))
    )
    (net (code "104") (name "unconnected-(J1-Pad12)") (class "Default")
      (node (ref "J1") (pin "12") (pinfunction "12_12") (pintype "passive"))
    )
    (net (code "105") (name "unconnected-(J1-Pad13)") (class "Default")
      (node (ref "J1") (pin "13") (pinfunction "13_13") (pintype "passive"))
    )
    (net (code "106") (name "unconnected-(J1-Pad14)") (class "Default")
      (node (ref "J1") (pin "14") (pinfunction "14_14") (pintype "passive"))
    )
    (net (code "107") (name "unconnected-(J1-Pad24)") (class "Default")
      (node (ref "J1") (pin "24") (pinfunction "24_24") (pintype "passive"))
    )
    (net (code "108") (name "unconnected-(J1-Pad26)") (class "Default")
      (node (ref "J1") (pin "26") (pinfunction "26_26") (pintype "passive"))
    )
    (net (code "109") (name "unconnected-(J1-Pad28)") (class "Default")
      (node (ref "J1") (pin "28") (pinfunction "28_28") (pintype "passive"))
    )
    (net (code "110") (name "unconnected-(J1-Pad30)") (class "Default")
      (node (ref "J1") (pin "30") (pinfunction "30_30") (pintype "passive"))
    )
  )
)
